# Sheet_1.net
KiCad netlist of a schematic drawn in Altium Designer
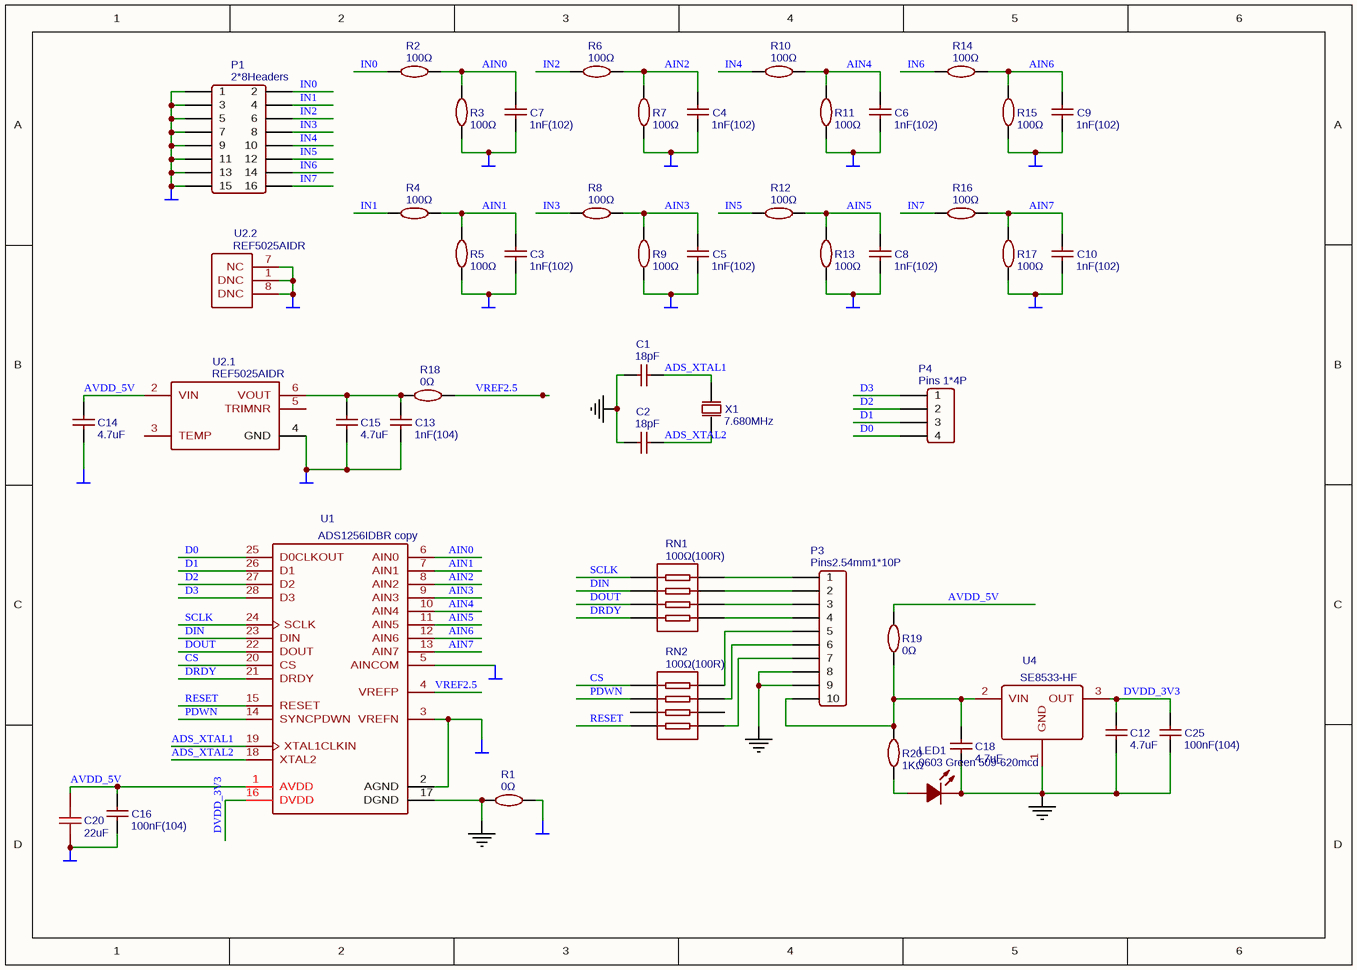
[diagram p0: Sheet_1.schdoc]

(export (version "E")
  (design (tool "Eeschema 10.0.6"))
  (components
    (comp (ref "C1")
      (value "18pF")
      (footprint "0603")
      (fields (field (name "BOM_MANUFACTURER PART") "CL10C180JB8NNNC"))
      (libsource (lib "") (part "root_0___3"))
    )
    (comp (ref "C2")
      (value "18pF")
      (footprint "0603")
      (fields (field (name "BOM_MANUFACTURER PART") "CL10C180JB8NNNC"))
      (libsource (lib "") (part "root_0___3"))
    )
    (comp (ref "C3")
      (value "1nF(102)")
      (footprint "0603")
      (fields (field (name "BOM_MANUFACTURER PART") "VJ0603Y102KXACW1BC") (field (name "CONTRIBUTOR") "LCSC"))
      (libsource (lib "altium-import") (part "root_1__"))
    )
    (comp (ref "C4")
      (value "1nF(102)")
      (footprint "0603")
      (fields (field (name "BOM_MANUFACTURER PART") "VJ0603Y102KXACW1BC") (field (name "CONTRIBUTOR") "LCSC"))
      (libsource (lib "altium-import") (part "root_1__"))
    )
    (comp (ref "C5")
      (value "1nF(102)")
      (footprint "0603")
      (fields (field (name "BOM_MANUFACTURER PART") "VJ0603Y102KXACW1BC") (field (name "CONTRIBUTOR") "LCSC"))
      (libsource (lib "altium-import") (part "root_1__"))
    )
    (comp (ref "C6")
      (value "1nF(102)")
      (footprint "0603")
      (fields (field (name "BOM_MANUFACTURER PART") "VJ0603Y102KXACW1BC") (field (name "CONTRIBUTOR") "LCSC"))
      (libsource (lib "altium-import") (part "root_1__"))
    )
    (comp (ref "C7")
      (value "1nF(102)")
      (footprint "0603")
      (fields (field (name "BOM_MANUFACTURER PART") "VJ0603Y102KXACW1BC") (field (name "CONTRIBUTOR") "LCSC"))
      (libsource (lib "altium-import") (part "root_1__"))
    )
    (comp (ref "C8")
      (value "1nF(102)")
      (footprint "0603")
      (fields (field (name "BOM_MANUFACTURER PART") "VJ0603Y102KXACW1BC") (field (name "CONTRIBUTOR") "LCSC"))
      (libsource (lib "altium-import") (part "root_1__"))
    )
    (comp (ref "C9")
      (value "1nF(102)")
      (footprint "0603")
      (fields (field (name "BOM_MANUFACTURER PART") "VJ0603Y102KXACW1BC") (field (name "CONTRIBUTOR") "LCSC"))
      (libsource (lib "altium-import") (part "root_1__"))
    )
    (comp (ref "C10")
      (value "1nF(102)")
      (footprint "0603")
      (fields (field (name "BOM_MANUFACTURER PART") "VJ0603Y102KXACW1BC") (field (name "CONTRIBUTOR") "LCSC"))
      (libsource (lib "altium-import") (part "root_1__"))
    )
    (comp (ref "C12")
      (value "4.7uF")
      (footprint "0805")
      (fields (field (name "BOM_MANUFACTURER PART") "CL21A475KOFNNNE"))
      (libsource (lib "") (part "root_1___1"))
    )
    (comp (ref "C13")
      (value "1nF(104)")
      (footprint "0805")
      (fields (field (name "BOM_MANUFACTURER PART") "08055C104JAT2A") (field (name "CONTRIBUTOR") "LCSC"))
      (libsource (lib "altium-import") (part "root_1__"))
    )
    (comp (ref "C14")
      (value "4.7uF")
      (footprint "0805")
      (fields (field (name "BOM_MANUFACTURER PART") "CL21A475KOFNNNE"))
      (libsource (lib "") (part "root_1___1"))
    )
    (comp (ref "C15")
      (value "4.7uF")
      (footprint "0805")
      (fields (field (name "BOM_MANUFACTURER PART") "CL21A475KOFNNNE"))
      (libsource (lib "") (part "root_1___1"))
    )
    (comp (ref "C16")
      (value "100nF(104)")
      (footprint "0805")
      (fields (field (name "BOM_MANUFACTURER PART") "08055C104JAT2A") (field (name "CONTRIBUTOR") "LCSC"))
      (libsource (lib "altium-import") (part "root_1__"))
    )
    (comp (ref "C18")
      (value "4.7uF")
      (footprint "0805")
      (fields (field (name "BOM_MANUFACTURER PART") "CL21A475KOFNNNE"))
      (libsource (lib "") (part "root_1___1"))
    )
    (comp (ref "C20")
      (value "22uF")
      (footprint "0805")
      (fields (field (name "BOM_MANUFACTURER PART") "0805X226M100NT"))
      (libsource (lib "") (part "root_1___2"))
    )
    (comp (ref "C25")
      (value "100nF(104)")
      (footprint "0805")
      (fields (field (name "BOM_MANUFACTURER PART") "08055C104JAT2A") (field (name "CONTRIBUTOR") "LCSC"))
      (libsource (lib "altium-import") (part "root_1__"))
    )
    (comp (ref "LED1")
      (value "0603 Green 509-620mcd")
      (footprint "LED-0603")
      (libsource (lib "") (part "root_0___10"))
    )
    (comp (ref "P1")
      (value "2*8Headers")
      (footprint "HDR-8X2/2.54")
      (fields (field (name "BOM_MANUFACTURER PART") "Double row straight 2*8Headers??Pins 2.54mm"))
      (libsource (lib "") (part "root_0___8"))
    )
    (comp (ref "P3")
      (value "Pins2.54mm1*10P")
      (footprint "HDR-10X1/2.54")
      (fields (field (name "BOM_MANUFACTURER PART") "Headers??Pins2.54mm1*10P"))
      (libsource (lib "") (part "root_0___6"))
    )
    (comp (ref "P4")
      (value "Pins 1*4P")
      (footprint "HDR-4X1/2.54")
      (fields (field (name "BOM_MANUFACTURER PART") "Headers??Pins 1*4P"))
      (libsource (lib "") (part "root_0___2"))
    )
    (comp (ref "R1")
      (value "0Ω")
      (footprint "0603")
      (fields (field (name "BOM_MANUFACTURER PART") "0603WAF0000T5E"))
      (libsource (lib "") (part "root_0___1"))
    )
    (comp (ref "R2")
      (value "100Ω")
      (footprint "0805")
      (fields (field (name "BOM_MANUFACTURER PART") "0805W8F1000T5E"))
      (libsource (lib "") (part "root_0___1"))
    )
    (comp (ref "R3")
      (value "100Ω")
      (footprint "0805")
      (fields (field (name "BOM_MANUFACTURER PART") "0805W8F1002T5E"))
      (libsource (lib "") (part "root_1___3"))
    )
    (comp (ref "R4")
      (value "100Ω")
      (footprint "0805")
      (fields (field (name "BOM_MANUFACTURER PART") "0805W8F1000T5E"))
      (libsource (lib "") (part "root_0___1"))
    )
    (comp (ref "R5")
      (value "100Ω")
      (footprint "0805")
      (fields (field (name "BOM_MANUFACTURER PART") "0805W8F1002T5E"))
      (libsource (lib "") (part "root_1___3"))
    )
    (comp (ref "R6")
      (value "100Ω")
      (footprint "0805")
      (fields (field (name "BOM_MANUFACTURER PART") "0805W8F1000T5E"))
      (libsource (lib "") (part "root_0___1"))
    )
    (comp (ref "R7")
      (value "100Ω")
      (footprint "0805")
      (fields (field (name "BOM_MANUFACTURER PART") "0805W8F1002T5E"))
      (libsource (lib "") (part "root_1___3"))
    )
    (comp (ref "R8")
      (value "100Ω")
      (footprint "0805")
      (fields (field (name "BOM_MANUFACTURER PART") "0805W8F1000T5E"))
      (libsource (lib "") (part "root_0___1"))
    )
    (comp (ref "R9")
      (value "100Ω")
      (footprint "0805")
      (fields (field (name "BOM_MANUFACTURER PART") "0805W8F1002T5E"))
      (libsource (lib "") (part "root_1___3"))
    )
    (comp (ref "R10")
      (value "100Ω")
      (footprint "0805")
      (fields (field (name "BOM_MANUFACTURER PART") "0805W8F1000T5E"))
      (libsource (lib "") (part "root_0___1"))
    )
    (comp (ref "R11")
      (value "100Ω")
      (footprint "0805")
      (fields (field (name "BOM_MANUFACTURER PART") "0805W8F1002T5E"))
      (libsource (lib "") (part "root_1___3"))
    )
    (comp (ref "R12")
      (value "100Ω")
      (footprint "0805")
      (fields (field (name "BOM_MANUFACTURER PART") "0805W8F1000T5E"))
      (libsource (lib "") (part "root_0___1"))
    )
    (comp (ref "R13")
      (value "100Ω")
      (footprint "0805")
      (fields (field (name "BOM_MANUFACTURER PART") "0805W8F1002T5E"))
      (libsource (lib "") (part "root_1___3"))
    )
    (comp (ref "R14")
      (value "100Ω")
      (footprint "0805")
      (fields (field (name "BOM_MANUFACTURER PART") "0805W8F1000T5E"))
      (libsource (lib "") (part "root_0___1"))
    )
    (comp (ref "R15")
      (value "100Ω")
      (footprint "0805")
      (fields (field (name "BOM_MANUFACTURER PART") "0805W8F1002T5E"))
      (libsource (lib "") (part "root_1___3"))
    )
    (comp (ref "R16")
      (value "100Ω")
      (footprint "0805")
      (fields (field (name "BOM_MANUFACTURER PART") "0805W8F1000T5E"))
      (libsource (lib "") (part "root_0___1"))
    )
    (comp (ref "R17")
      (value "100Ω")
      (footprint "0805")
      (fields (field (name "BOM_MANUFACTURER PART") "0805W8F1002T5E"))
      (libsource (lib "") (part "root_1___3"))
    )
    (comp (ref "R18")
      (value "0Ω")
      (footprint "0603")
      (fields (field (name "BOM_MANUFACTURER PART") "0603WAF0000T5E"))
      (libsource (lib "") (part "root_0___1"))
    )
    (comp (ref "R19")
      (value "0Ω")
      (footprint "0603")
      (fields (field (name "BOM_MANUFACTURER PART") "0603WAF0000T5E"))
      (libsource (lib "") (part "root_1___3"))
    )
    (comp (ref "R20")
      (value "1KΩ")
      (footprint "0603")
      (fields (field (name "BOM_MANUFACTURER PART") "0603WAJ0102T5E"))
      (libsource (lib "") (part "root_1___3"))
    )
    (comp (ref "RN1")
      (value "100Ω(100R)")
      (footprint "0603_X4")
      (fields (field (name "BOM_MANUFACTURER PART") "YC164-FR-07100RL"))
      (libsource (lib "") (part "root_0___4"))
    )
    (comp (ref "RN2")
      (value "100Ω(100R)")
      (footprint "0603_X4")
      (fields (field (name "BOM_MANUFACTURER PART") "YC164-FR-07100RL"))
      (libsource (lib "") (part "root_0___4"))
    )
    (comp (ref "U1")
      (value "ADS1256IDBR copy")
      (footprint "SSOP-28_208MIL")
      (fields (field (name "BOM_MANUFACTURER PART") "ADS1256IDBR"))
      (libsource (lib "") (part "root_0___7"))
    )
    (comp (ref "U2.1")
      (value "REF5025AIDR")
      (footprint "SOIC-8_150MIL")
      (fields (field (name "SUBPART_NO") "1"))
      (libsource (lib "") (part "root_0___5"))
    )
    (comp (ref "U2.2")
      (value "REF5025AIDR")
      (footprint "SOIC-8_150MIL")
      (fields (field (name "SUBPART_NO") "2"))
      (libsource (lib "altium-import") (part "root_0__"))
    )
    (comp (ref "U4")
      (value "SE8533-HF")
      (footprint "SOT-89(SOT-89-3)")
      (libsource (lib "") (part "root_0___9"))
    )
    (comp (ref "X1")
      (value "7.680MHz")
      (footprint "OSC-49S-1")
      (fields (field (name "BOM_MANUFACTURER PART") "X49SD8MSD2SC"))
      (libsource (lib "") (part "root_1___4"))
    )
  )
  (nets
    (net (code "1") (name "/ADS_XTAL1") (class "Default")
      (node (ref "C1") (pin "2") (pinfunction "2_2") (pintype "passive"))
      (node (ref "U1") (pin "19") (pinfunction "XTAL1CLKIN_19") (pintype "passive"))
      (node (ref "X1") (pin "1") (pinfunction "OSC1_1") (pintype "passive"))
    )
    (net (code "2") (name "/ADS_XTAL2") (class "Default")
      (node (ref "C2") (pin "2") (pinfunction "2_2") (pintype "passive"))
      (node (ref "U1") (pin "18") (pinfunction "XTAL2_18") (pintype "passive"))
      (node (ref "X1") (pin "2") (pinfunction "OSC2_2") (pintype "passive"))
    )
    (net (code "3") (name "/AIN0") (class "Default")
      (node (ref "C7") (pin "2") (pinfunction "2_2") (pintype "passive"))
      (node (ref "R2") (pin "2") (pinfunction "2_2") (pintype "passive"))
      (node (ref "R3") (pin "2") (pinfunction "2_2") (pintype "passive"))
      (node (ref "U1") (pin "6") (pinfunction "AIN0_6") (pintype "passive"))
    )
    (net (code "4") (name "/AIN1") (class "Default")
      (node (ref "C3") (pin "2") (pinfunction "2_2") (pintype "passive"))
      (node (ref "R4") (pin "2") (pinfunction "2_2") (pintype "passive"))
      (node (ref "R5") (pin "2") (pinfunction "2_2") (pintype "passive"))
      (node (ref "U1") (pin "7") (pinfunction "AIN1_7") (pintype "passive"))
    )
    (net (code "5") (name "/AIN2") (class "Default")
      (node (ref "C4") (pin "2") (pinfunction "2_2") (pintype "passive"))
      (node (ref "R6") (pin "2") (pinfunction "2_2") (pintype "passive"))
      (node (ref "R7") (pin "2") (pinfunction "2_2") (pintype "passive"))
      (node (ref "U1") (pin "8") (pinfunction "AIN2_8") (pintype "passive"))
    )
    (net (code "6") (name "/AIN3") (class "Default")
      (node (ref "C5") (pin "2") (pinfunction "2_2") (pintype "passive"))
      (node (ref "R8") (pin "2") (pinfunction "2_2") (pintype "passive"))
      (node (ref "R9") (pin "2") (pinfunction "2_2") (pintype "passive"))
      (node (ref "U1") (pin "9") (pinfunction "AIN3_9") (pintype "passive"))
    )
    (net (code "7") (name "/AIN4") (class "Default")
      (node (ref "C6") (pin "2") (pinfunction "2_2") (pintype "passive"))
      (node (ref "R10") (pin "2") (pinfunction "2_2") (pintype "passive"))
      (node (ref "R11") (pin "2") (pinfunction "2_2") (pintype "passive"))
      (node (ref "U1") (pin "10") (pinfunction "AIN4_10") (pintype "passive"))
    )
    (net (code "8") (name "/AIN5") (class "Default")
      (node (ref "C8") (pin "2") (pinfunction "2_2") (pintype "passive"))
      (node (ref "R12") (pin "2") (pinfunction "2_2") (pintype "passive"))
      (node (ref "R13") (pin "2") (pinfunction "2_2") (pintype "passive"))
      (node (ref "U1") (pin "11") (pinfunction "AIN5_11") (pintype "passive"))
    )
    (net (code "9") (name "/AIN6") (class "Default")
      (node (ref "C9") (pin "2") (pinfunction "2_2") (pintype "passive"))
      (node (ref "R14") (pin "2") (pinfunction "2_2") (pintype "passive"))
      (node (ref "R15") (pin "2") (pinfunction "2_2") (pintype "passive"))
      (node (ref "U1") (pin "12") (pinfunction "AIN6_12") (pintype "passive"))
    )
    (net (code "10") (name "/AIN7") (class "Default")
      (node (ref "C10") (pin "2") (pinfunction "2_2") (pintype "passive"))
      (node (ref "R16") (pin "2") (pinfunction "2_2") (pintype "passive"))
      (node (ref "R17") (pin "2") (pinfunction "2_2") (pintype "passive"))
      (node (ref "U1") (pin "13") (pinfunction "AIN7_13") (pintype "passive"))
    )
    (net (code "11") (name "/AVDD_5V") (class "Default")
      (node (ref "C14") (pin "2") (pinfunction "2_2") (pintype "passive"))
      (node (ref "C16") (pin "2") (pinfunction "2_2") (pintype "passive"))
      (node (ref "C20") (pin "2") (pinfunction "2_2") (pintype "passive"))
      (node (ref "R19") (pin "2") (pinfunction "2_2") (pintype "passive"))
      (node (ref "U1") (pin "1") (pinfunction "AVDD_1") (pintype "passive"))
      (node (ref "U2.1") (pin "2") (pinfunction "VIN_2") (pintype "passive"))
    )
    (net (code "12") (name "/CS") (class "Default")
      (node (ref "RN2") (pin "1") (pinfunction "1_1") (pintype "passive"))
      (node (ref "U1") (pin "20") (pinfunction "CS_20") (pintype "passive"))
    )
    (net (code "13") (name "/D0") (class "Default")
      (node (ref "P4") (pin "4") (pinfunction "4_4") (pintype "passive"))
      (node (ref "U1") (pin "25") (pinfunction "D0CLKOUT_25") (pintype "passive"))
    )
    (net (code "14") (name "/D1") (class "Default")
      (node (ref "P4") (pin "3") (pinfunction "3_3") (pintype "passive"))
      (node (ref "U1") (pin "26") (pinfunction "D1_26") (pintype "passive"))
    )
    (net (code "15") (name "/D2") (class "Default")
      (node (ref "P4") (pin "2") (pinfunction "2_2") (pintype "passive"))
      (node (ref "U1") (pin "27") (pinfunction "D2_27") (pintype "passive"))
    )
    (net (code "16") (name "/D3") (class "Default")
      (node (ref "P4") (pin "1") (pinfunction "1_1") (pintype "passive"))
      (node (ref "U1") (pin "28") (pinfunction "D3_28") (pintype "passive"))
    )
    (net (code "17") (name "/DIN") (class "Default")
      (node (ref "RN1") (pin "2") (pinfunction "2_2") (pintype "passive"))
      (node (ref "U1") (pin "23") (pinfunction "DIN_23") (pintype "passive"))
    )
    (net (code "18") (name "/DOUT") (class "Default")
      (node (ref "RN1") (pin "3") (pinfunction "3_3") (pintype "passive"))
      (node (ref "U1") (pin "22") (pinfunction "DOUT_22") (pintype "passive"))
    )
    (net (code "19") (name "/DRDY") (class "Default")
      (node (ref "RN1") (pin "4") (pinfunction "4_4") (pintype "passive"))
      (node (ref "U1") (pin "21") (pinfunction "DRDY_21") (pintype "passive"))
    )
    (net (code "20") (name "/DVDD_3V3") (class "Default")
      (node (ref "C12") (pin "2") (pinfunction "2_2") (pintype "passive"))
      (node (ref "C25") (pin "2") (pinfunction "2_2") (pintype "passive"))
      (node (ref "U1") (pin "16") (pinfunction "DVDD_16") (pintype "passive"))
      (node (ref "U4") (pin "3") (pinfunction "OUT_3") (pintype "passive"))
    )
    (net (code "21") (name "/IN0") (class "Default")
      (node (ref "P1") (pin "2") (pinfunction "2_2") (pintype "passive"))
      (node (ref "R2") (pin "1") (pinfunction "1_1") (pintype "passive"))
    )
    (net (code "22") (name "/IN1") (class "Default")
      (node (ref "P1") (pin "4") (pinfunction "4_4") (pintype "passive"))
      (node (ref "R4") (pin "1") (pinfunction "1_1") (pintype "passive"))
    )
    (net (code "23") (name "/IN2") (class "Default")
      (node (ref "P1") (pin "6") (pinfunction "6_6") (pintype "passive"))
      (node (ref "R6") (pin "1") (pinfunction "1_1") (pintype "passive"))
    )
    (net (code "24") (name "/IN3") (class "Default")
      (node (ref "P1") (pin "8") (pinfunction "8_8") (pintype "passive"))
      (node (ref "R8") (pin "1") (pinfunction "1_1") (pintype "passive"))
    )
    (net (code "25") (name "/IN4") (class "Default")
      (node (ref "P1") (pin "10") (pinfunction "10_10") (pintype "passive"))
      (node (ref "R10") (pin "1") (pinfunction "1_1") (pintype "passive"))
    )
    (net (code "26") (name "/IN5") (class "Default")
      (node (ref "P1") (pin "12") (pinfunction "12_12") (pintype "passive"))
      (node (ref "R12") (pin "1") (pinfunction "1_1") (pintype "passive"))
    )
    (net (code "27") (name "/IN6") (class "Default")
      (node (ref "P1") (pin "14") (pinfunction "14_14") (pintype "passive"))
      (node (ref "R14") (pin "1") (pinfunction "1_1") (pintype "passive"))
    )
    (net (code "28") (name "/IN7") (class "Default")
      (node (ref "P1") (pin "16") (pinfunction "16_16") (pintype "passive"))
      (node (ref "R16") (pin "1") (pinfunction "1_1") (pintype "passive"))
    )
    (net (code "29") (name "/PDWN") (class "Default")
      (node (ref "RN2") (pin "2") (pinfunction "2_2") (pintype "passive"))
      (node (ref "U1") (pin "14") (pinfunction "SYNCPDWN_14") (pintype "passive"))
    )
    (net (code "30") (name "/RESET") (class "Default")
      (node (ref "RN2") (pin "4") (pinfunction "4_4") (pintype "passive"))
      (node (ref "U1") (pin "15") (pinfunction "RESET_15") (pintype "passive"))
    )
    (net (code "31") (name "/SCLK") (class "Default")
      (node (ref "RN1") (pin "1") (pinfunction "1_1") (pintype "passive"))
      (node (ref "U1") (pin "24") (pinfunction "SCLK_24") (pintype "passive"))
    )
    (net (code "32") (name "/VREF2.5") (class "Default")
      (node (ref "R18") (pin "2") (pinfunction "2_2") (pintype "passive"))
      (node (ref "U1") (pin "4") (pinfunction "VREFP_4") (pintype "passive"))
    )
    (net (code "33") (name "AGND") (class "Default")
      (node (ref "C10") (pin "1") (pinfunction "1_1") (pintype "passive"))
      (node (ref "C13") (pin "1") (pinfunction "1_1") (pintype "passive"))
      (node (ref "C14") (pin "1") (pinfunction "1_1") (pintype "passive"))
      (node (ref "C15") (pin "1") (pinfunction "1_1") (pintype "passive"))
      (node (ref "C16") (pin "1") (pinfunction "1_1") (pintype "passive"))
      (node (ref "C20") (pin "1") (pinfunction "1_1") (pintype "passive"))
      (node (ref "C3") (pin "1") (pinfunction "1_1") (pintype "passive"))
      (node (ref "C4") (pin "1") (pinfunction "1_1") (pintype "passive"))
      (node (ref "C5") (pin "1") (pinfunction "1_1") (pintype "passive"))
      (node (ref "C6") (pin "1") (pinfunction "1_1") (pintype "passive"))
      (node (ref "C7") (pin "1") (pinfunction "1_1") (pintype "passive"))
      (node (ref "C8") (pin "1") (pinfunction "1_1") (pintype "passive"))
      (node (ref "C9") (pin "1") (pinfunction "1_1") (pintype "passive"))
      (node (ref "P1") (pin "1") (pinfunction "1_1") (pintype "passive"))
      (node (ref "P1") (pin "11") (pinfunction "11_11") (pintype "passive"))
      (node (ref "P1") (pin "13") (pinfunction "13_13") (pintype "passive"))
      (node (ref "P1") (pin "15") (pinfunction "15_15") (pintype "passive"))
      (node (ref "P1") (pin "3") (pinfunction "3_3") (pintype "passive"))
      (node (ref "P1") (pin "5") (pinfunction "5_5") (pintype "passive"))
      (node (ref "P1") (pin "7") (pinfunction "7_7") (pintype "passive"))
      (node (ref "P1") (pin "9") (pinfunction "9_9") (pintype "passive"))
      (node (ref "R1") (pin "2") (pinfunction "2_2") (pintype "passive"))
      (node (ref "R11") (pin "1") (pinfunction "1_1") (pintype "passive"))
      (node (ref "R13") (pin "1") (pinfunction "1_1") (pintype "passive"))
      (node (ref "R15") (pin "1") (pinfunction "1_1") (pintype "passive"))
      (node (ref "R17") (pin "1") (pinfunction "1_1") (pintype "passive"))
      (node (ref "R3") (pin "1") (pinfunction "1_1") (pintype "passive"))
      (node (ref "R5") (pin "1") (pinfunction "1_1") (pintype "passive"))
      (node (ref "R7") (pin "1") (pinfunction "1_1") (pintype "passive"))
      (node (ref "R9") (pin "1") (pinfunction "1_1") (pintype "passive"))
      (node (ref "U1") (pin "2") (pinfunction "AGND_2") (pintype "passive"))
      (node (ref "U1") (pin "3") (pinfunction "VREFN_3") (pintype "passive"))
      (node (ref "U1") (pin "5") (pinfunction "AINCOM_5") (pintype "passive"))
      (node (ref "U2.1") (pin "4") (pinfunction "GND_4") (pintype "passive"))
      (node (ref "U2.2") (pin "1") (pinfunction "DNC_1") (pintype "passive"))
      (node (ref "U2.2") (pin "7") (pinfunction "NC_7") (pintype "passive"))
      (node (ref "U2.2") (pin "8") (pinfunction "DNC_8") (pintype "passive"))
    )
    (net (code "34") (name "DGND") (class "Default")
      (node (ref "C1") (pin "1") (pinfunction "1_1") (pintype "passive"))
      (node (ref "C12") (pin "1") (pinfunction "1_1") (pintype "passive"))
      (node (ref "C18") (pin "1") (pinfunction "1_1") (pintype "passive"))
      (node (ref "C2") (pin "1") (pinfunction "1_1") (pintype "passive"))
      (node (ref "C25") (pin "1") (pinfunction "1_1") (pintype "passive"))
      (node (ref "LED1") (pin "2") (pinfunction "K_2") (pintype "passive"))
      (node (ref "P3") (pin "8") (pinfunction "8_8") (pintype "passive"))
      (node (ref "P3") (pin "9") (pinfunction "9_9") (pintype "passive"))
      (node (ref "R1") (pin "1") (pinfunction "1_1") (pintype "passive"))
      (node (ref "U1") (pin "17") (pinfunction "DGND_17") (pintype "passive"))
      (node (ref "U4") (pin "1") (pinfunction "GND_1") (pintype "passive"))
    )
    (net (code "35") (name "Net-(LED1-A)") (class "Default")
      (node (ref "LED1") (pin "1") (pinfunction "A_1") (pintype "passive"))
      (node (ref "R20") (pin "1") (pinfunction "1_1") (pintype "passive"))
    )
    (net (code "36") (name "Net-(P3-Pad1)") (class "Default")
      (node (ref "P3") (pin "1") (pinfunction "1_1") (pintype "passive"))
      (node (ref "RN1") (pin "8") (pinfunction "8_8") (pintype "passive"))
    )
    (net (code "37") (name "Net-(P3-Pad2)") (class "Default")
      (node (ref "P3") (pin "2") (pinfunction "2_2") (pintype "passive"))
      (node (ref "RN1") (pin "7") (pinfunction "7_7") (pintype "passive"))
    )
    (net (code "38") (name "Net-(P3-Pad3)") (class "Default")
      (node (ref "P3") (pin "3") (pinfunction "3_3") (pintype "passive"))
      (node (ref "RN1") (pin "6") (pinfunction "6_6") (pintype "passive"))
    )
    (net (code "39") (name "Net-(P3-Pad4)") (class "Default")
      (node (ref "P3") (pin "4") (pinfunction "4_4") (pintype "passive"))
      (node (ref "RN1") (pin "5") (pinfunction "5_5") (pintype "passive"))
    )
    (net (code "40") (name "Net-(P3-Pad5)") (class "Default")
      (node (ref "P3") (pin "5") (pinfunction "5_5") (pintype "passive"))
      (node (ref "RN2") (pin "8") (pinfunction "8_8") (pintype "passive"))
    )
    (net (code "41") (name "Net-(P3-Pad6)") (class "Default")
      (node (ref "P3") (pin "6") (pinfunction "6_6") (pintype "passive"))
      (node (ref "RN2") (pin "7") (pinfunction "7_7") (pintype "passive"))
    )
    (net (code "42") (name "Net-(P3-Pad7)") (class "Default")
      (node (ref "P3") (pin "7") (pinfunction "7_7") (pintype "passive"))
      (node (ref "RN2") (pin "5") (pinfunction "5_5") (pintype "passive"))
    )
    (net (code "43") (name "Net-(U2.1-VOUT)") (class "Default")
      (node (ref "C13") (pin "2") (pinfunction "2_2") (pintype "passive"))
      (node (ref "C15") (pin "2") (pinfunction "2_2") (pintype "passive"))
      (node (ref "R18") (pin "1") (pinfunction "1_1") (pintype "passive"))
      (node (ref "U2.1") (pin "6") (pinfunction "VOUT_6") (pintype "passive"))
    )
    (net (code "44") (name "Net-(U4-VIN)") (class "Default")
      (node (ref "C18") (pin "2") (pinfunction "2_2") (pintype "passive"))
      (node (ref "P3") (pin "10") (pinfunction "10_10") (pintype "passive"))
      (node (ref "R19") (pin "1") (pinfunction "1_1") (pintype "passive"))
      (node (ref "R20") (pin "2") (pinfunction "2_2") (pintype "passive"))
      (node (ref "U4") (pin "2") (pinfunction "VIN_2") (pintype "passive"))
    )
    (net (code "45") (name "unconnected-(RN2-Pad3)") (class "Default")
      (node (ref "RN2") (pin "3") (pinfunction "3_3") (pintype "passive"))
    )
    (net (code "46") (name "unconnected-(RN2-Pad6)") (class "Default")
      (node (ref "RN2") (pin "6") (pinfunction "6_6") (pintype "passive"))
    )
    (net (code "47") (name "unconnected-(U2.1-TEMP-Pad3)") (class "Default")
      (node (ref "U2.1") (pin "3") (pinfunction "TEMP_3") (pintype "passive"))
    )
    (net (code "48") (name "unconnected-(U2.1-TRIMNR-Pad5)") (class "Default")
      (node (ref "U2.1") (pin "5") (pinfunction "TRIMNR_5") (pintype "passive"))
    )
  )
)
